# Slipring_Brush.net
KiCad netlist of a schematic drawn in EAGLE
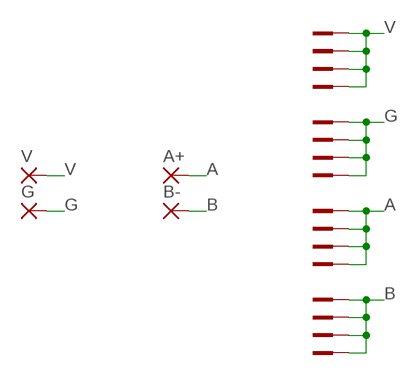
[diagram p0: schematic, sheet 1]

(export (version "E")
  (design (tool "Eeschema 10.0.6"))
  (components
    (comp (ref "A+")
      (value "SMD2")
      (footprint "eagle-import:SMD1,27-2,54")
      (libsource (lib "eagle-import") (part "SMD2"))
    )
    (comp (ref "B-")
      (value "SMD2")
      (footprint "eagle-import:SMD1,27-2,54")
      (libsource (lib "eagle-import") (part "SMD2"))
    )
    (comp (ref "G")
      (value "SMD2")
      (footprint "eagle-import:SMD1,27-2,54")
      (libsource (lib "eagle-import") (part "SMD2"))
    )
    (comp (ref "U$1")
      (value "POGOPIN_A585")
      (footprint "eagle-import:POGOPIN_A585")
      (libsource (lib "eagle-import") (part "POGOPIN_A585"))
    )
    (comp (ref "U$2")
      (value "POGOPIN_A585")
      (footprint "eagle-import:POGOPIN_A585")
      (libsource (lib "eagle-import") (part "POGOPIN_A585"))
    )
    (comp (ref "U$3")
      (value "POGOPIN_A585")
      (footprint "eagle-import:POGOPIN_A585")
      (libsource (lib "eagle-import") (part "POGOPIN_A585"))
    )
    (comp (ref "U$4")
      (value "POGOPIN_A585")
      (footprint "eagle-import:POGOPIN_A585")
      (libsource (lib "eagle-import") (part "POGOPIN_A585"))
    )
    (comp (ref "U$5")
      (value "POGOPIN_A585")
      (footprint "eagle-import:POGOPIN_A585")
      (libsource (lib "eagle-import") (part "POGOPIN_A585"))
    )
    (comp (ref "U$6")
      (value "POGOPIN_A585")
      (footprint "eagle-import:POGOPIN_A585")
      (libsource (lib "eagle-import") (part "POGOPIN_A585"))
    )
    (comp (ref "U$7")
      (value "POGOPIN_A585")
      (footprint "eagle-import:POGOPIN_A585")
      (libsource (lib "eagle-import") (part "POGOPIN_A585"))
    )
    (comp (ref "U$8")
      (value "POGOPIN_A585")
      (footprint "eagle-import:POGOPIN_A585")
      (libsource (lib "eagle-import") (part "POGOPIN_A585"))
    )
    (comp (ref "U$9")
      (value "POGOPIN_A585")
      (footprint "eagle-import:POGOPIN_A585")
      (libsource (lib "eagle-import") (part "POGOPIN_A585"))
    )
    (comp (ref "U$10")
      (value "POGOPIN_A585")
      (footprint "eagle-import:POGOPIN_A585")
      (libsource (lib "eagle-import") (part "POGOPIN_A585"))
    )
    (comp (ref "U$11")
      (value "POGOPIN_A585")
      (footprint "eagle-import:POGOPIN_A585")
      (libsource (lib "eagle-import") (part "POGOPIN_A585"))
    )
    (comp (ref "U$12")
      (value "POGOPIN_A585")
      (footprint "eagle-import:POGOPIN_A585")
      (libsource (lib "eagle-import") (part "POGOPIN_A585"))
    )
    (comp (ref "U$13")
      (value "POGOPIN_A585")
      (footprint "eagle-import:POGOPIN_A585")
      (libsource (lib "eagle-import") (part "POGOPIN_A585"))
    )
    (comp (ref "U$14")
      (value "POGOPIN_A585")
      (footprint "eagle-import:POGOPIN_A585")
      (libsource (lib "eagle-import") (part "POGOPIN_A585"))
    )
    (comp (ref "U$15")
      (value "POGOPIN_A585")
      (footprint "eagle-import:POGOPIN_A585")
      (libsource (lib "eagle-import") (part "POGOPIN_A585"))
    )
    (comp (ref "U$16")
      (value "POGOPIN_A585")
      (footprint "eagle-import:POGOPIN_A585")
      (libsource (lib "eagle-import") (part "POGOPIN_A585"))
    )
    (comp (ref "V")
      (value "SMD2")
      (footprint "eagle-import:SMD1,27-2,54")
      (libsource (lib "eagle-import") (part "SMD2"))
    )
  )
  (nets
    (net (code "1") (name "/A") (class "Default")
      (node (ref "A+") (pin "1") (pinfunction "P_1") (pintype "passive"))
      (node (ref "U$10") (pin "P$1") (pinfunction "KL_P$1") (pintype "passive"))
      (node (ref "U$10") (pin "P$2") (pinfunction "KL_P$2") (pintype "passive"))
      (node (ref "U$10") (pin "P$3") (pinfunction "KL_P$3") (pintype "passive"))
      (node (ref "U$11") (pin "P$1") (pinfunction "KL_P$1") (pintype "passive"))
      (node (ref "U$11") (pin "P$2") (pinfunction "KL_P$2") (pintype "passive"))
      (node (ref "U$11") (pin "P$3") (pinfunction "KL_P$3") (pintype "passive"))
      (node (ref "U$12") (pin "P$1") (pinfunction "KL_P$1") (pintype "passive"))
      (node (ref "U$12") (pin "P$2") (pinfunction "KL_P$2") (pintype "passive"))
      (node (ref "U$12") (pin "P$3") (pinfunction "KL_P$3") (pintype "passive"))
      (node (ref "U$9") (pin "P$1") (pinfunction "KL_P$1") (pintype "passive"))
      (node (ref "U$9") (pin "P$2") (pinfunction "KL_P$2") (pintype "passive"))
      (node (ref "U$9") (pin "P$3") (pinfunction "KL_P$3") (pintype "passive"))
    )
    (net (code "2") (name "/B") (class "Default")
      (node (ref "B-") (pin "1") (pinfunction "P_1") (pintype "passive"))
      (node (ref "U$13") (pin "P$1") (pinfunction "KL_P$1") (pintype "passive"))
      (node (ref "U$13") (pin "P$2") (pinfunction "KL_P$2") (pintype "passive"))
      (node (ref "U$13") (pin "P$3") (pinfunction "KL_P$3") (pintype "passive"))
      (node (ref "U$14") (pin "P$1") (pinfunction "KL_P$1") (pintype "passive"))
      (node (ref "U$14") (pin "P$2") (pinfunction "KL_P$2") (pintype "passive"))
      (node (ref "U$14") (pin "P$3") (pinfunction "KL_P$3") (pintype "passive"))
      (node (ref "U$15") (pin "P$1") (pinfunction "KL_P$1") (pintype "passive"))
      (node (ref "U$15") (pin "P$2") (pinfunction "KL_P$2") (pintype "passive"))
      (node (ref "U$15") (pin "P$3") (pinfunction "KL_P$3") (pintype "passive"))
      (node (ref "U$16") (pin "P$1") (pinfunction "KL_P$1") (pintype "passive"))
      (node (ref "U$16") (pin "P$2") (pinfunction "KL_P$2") (pintype "passive"))
      (node (ref "U$16") (pin "P$3") (pinfunction "KL_P$3") (pintype "passive"))
    )
    (net (code "3") (name "/G") (class "Default")
      (node (ref "G") (pin "1") (pinfunction "P_1") (pintype "passive"))
      (node (ref "U$5") (pin "P$1") (pinfunction "KL_P$1") (pintype "passive"))
      (node (ref "U$5") (pin "P$2") (pinfunction "KL_P$2") (pintype "passive"))
      (node (ref "U$5") (pin "P$3") (pinfunction "KL_P$3") (pintype "passive"))
      (node (ref "U$6") (pin "P$1") (pinfunction "KL_P$1") (pintype "passive"))
      (node (ref "U$6") (pin "P$2") (pinfunction "KL_P$2") (pintype "passive"))
      (node (ref "U$6") (pin "P$3") (pinfunction "KL_P$3") (pintype "passive"))
      (node (ref "U$7") (pin "P$1") (pinfunction "KL_P$1") (pintype "passive"))
      (node (ref "U$7") (pin "P$2") (pinfunction "KL_P$2") (pintype "passive"))
      (node (ref "U$7") (pin "P$3") (pinfunction "KL_P$3") (pintype "passive"))
      (node (ref "U$8") (pin "P$1") (pinfunction "KL_P$1") (pintype "passive"))
      (node (ref "U$8") (pin "P$2") (pinfunction "KL_P$2") (pintype "passive"))
      (node (ref "U$8") (pin "P$3") (pinfunction "KL_P$3") (pintype "passive"))
    )
    (net (code "4") (name "/V") (class "Default")
      (node (ref "U$1") (pin "P$1") (pinfunction "KL_P$1") (pintype "passive"))
      (node (ref "U$1") (pin "P$2") (pinfunction "KL_P$2") (pintype "passive"))
      (node (ref "U$1") (pin "P$3") (pinfunction "KL_P$3") (pintype "passive"))
      (node (ref "U$2") (pin "P$1") (pinfunction "KL_P$1") (pintype "passive"))
      (node (ref "U$2") (pin "P$2") (pinfunction "KL_P$2") (pintype "passive"))
      (node (ref "U$2") (pin "P$3") (pinfunction "KL_P$3") (pintype "passive"))
      (node (ref "U$3") (pin "P$1") (pinfunction "KL_P$1") (pintype "passive"))
      (node (ref "U$3") (pin "P$2") (pinfunction "KL_P$2") (pintype "passive"))
      (node (ref "U$3") (pin "P$3") (pinfunction "KL_P$3") (pintype "passive"))
      (node (ref "U$4") (pin "P$1") (pinfunction "KL_P$1") (pintype "passive"))
      (node (ref "U$4") (pin "P$2") (pinfunction "KL_P$2") (pintype "passive"))
      (node (ref "U$4") (pin "P$3") (pinfunction "KL_P$3") (pintype "passive"))
      (node (ref "V") (pin "1") (pinfunction "P_1") (pintype "passive"))
    )
  )
)
